# mic_sensor_arduino.net
KiCad netlist of a schematic drawn in EAGLE
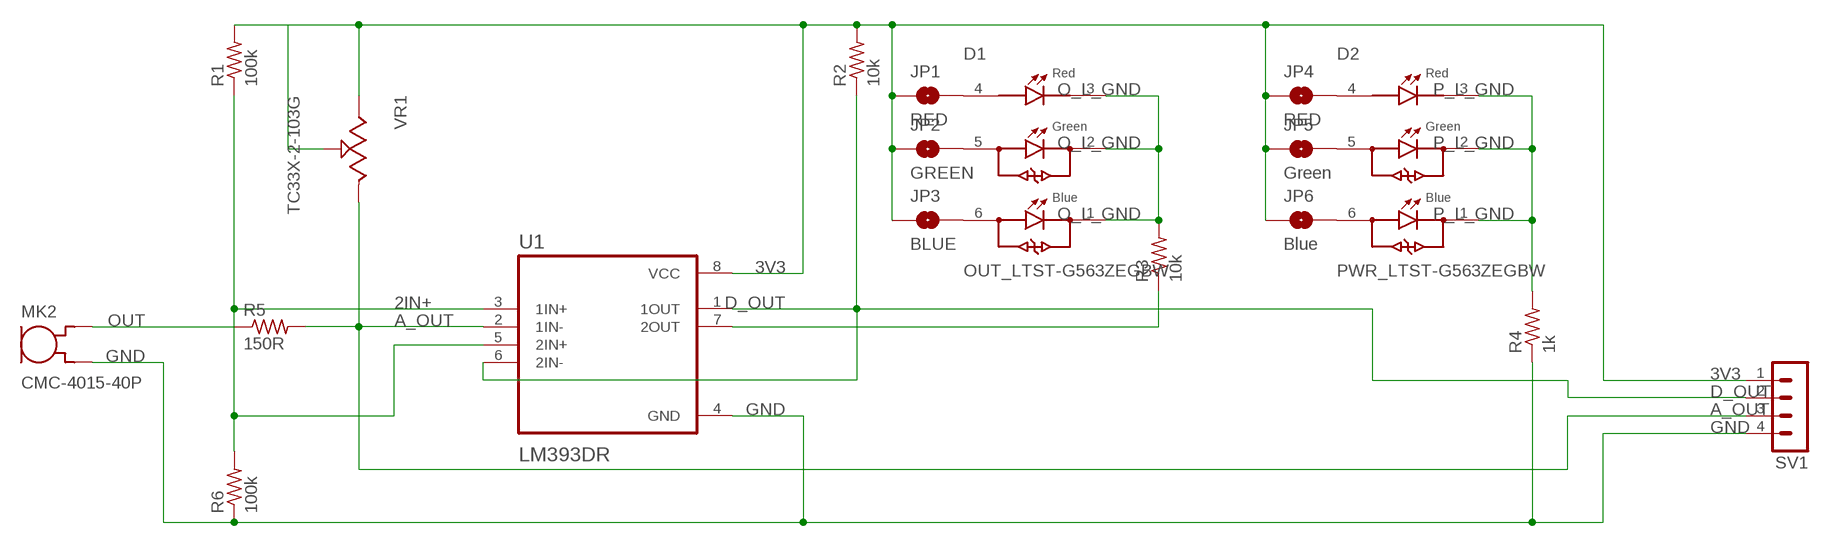
[diagram p0: schematic, sheet 1]

(export (version "E")
  (design (tool "Eeschema 10.0.6"))
  (components
    (comp (ref "D1")
      (value "OUT_LTST-G563ZEGBW")
      (footprint "eagle-import:LED_LTST-G563ZEGBW")
      (fields (field (name "MF") "Lite-On") (field (name "MP") "LTST-G563ZEGBW"))
      (libsource (lib "eagle-import") (part "LTST-G563ZEGBW"))
    )
    (comp (ref "D2")
      (value "PWR_LTST-G563ZEGBW")
      (footprint "eagle-import:LED_LTST-G563ZEGBW")
      (fields (field (name "MF") "Lite-On") (field (name "MP") "LTST-G563ZEGBW"))
      (libsource (lib "eagle-import") (part "LTST-G563ZEGBW"))
    )
    (comp (ref "JP1")
      (value "RED")
      (footprint "eagle-import:SMT-JUMPER_2_NO_SILK")
      (libsource (lib "eagle-import") (part "JUMPER-SMT_2_NO_SILK"))
    )
    (comp (ref "JP2")
      (value "GREEN")
      (footprint "eagle-import:SMT-JUMPER_2_NO_SILK")
      (libsource (lib "eagle-import") (part "JUMPER-SMT_2_NO_SILK"))
    )
    (comp (ref "JP3")
      (value "BLUE")
      (footprint "eagle-import:SMT-JUMPER_2_NO_SILK")
      (libsource (lib "eagle-import") (part "JUMPER-SMT_2_NO_SILK"))
    )
    (comp (ref "JP4")
      (value "RED")
      (footprint "eagle-import:SMT-JUMPER_2_NO_SILK")
      (libsource (lib "eagle-import") (part "JUMPER-SMT_2_NO_SILK"))
    )
    (comp (ref "JP5")
      (value "Green")
      (footprint "eagle-import:SMT-JUMPER_2_NO_SILK")
      (libsource (lib "eagle-import") (part "JUMPER-SMT_2_NO_SILK"))
    )
    (comp (ref "JP6")
      (value "Blue")
      (footprint "eagle-import:SMT-JUMPER_2_NO_SILK")
      (libsource (lib "eagle-import") (part "JUMPER-SMT_2_NO_SILK"))
    )
    (comp (ref "MK2")
      (value "CMC-4015-40P")
      (footprint "eagle-import:MIC_CMC-4015-40P")
      (fields (field (name "MF") "CUI Devices"))
      (libsource (lib "eagle-import") (part "CMC-4015-40P"))
    )
    (comp (ref "R1")
      (value "100k")
      (footprint "eagle-import:R0603")
      (libsource (lib "eagle-import") (part "R-US_R0603"))
    )
    (comp (ref "R2")
      (value "10k")
      (footprint "eagle-import:R0603")
      (libsource (lib "eagle-import") (part "R-US_R0603"))
    )
    (comp (ref "R3")
      (value "10k")
      (footprint "eagle-import:R0603")
      (libsource (lib "eagle-import") (part "R-US_R0603"))
    )
    (comp (ref "R4")
      (value "1k")
      (footprint "eagle-import:R0603")
      (libsource (lib "eagle-import") (part "R-US_R0603"))
    )
    (comp (ref "R5")
      (value "150R")
      (footprint "eagle-import:R0603")
      (libsource (lib "eagle-import") (part "R-US_R0603"))
    )
    (comp (ref "R6")
      (value "100k")
      (footprint "eagle-import:R0603")
      (libsource (lib "eagle-import") (part "R-US_R0603"))
    )
    (comp (ref "SV1")
      (value "MA04-1")
      (footprint "eagle-import:MA04-1")
      (libsource (lib "eagle-import") (part "MA04-1"))
    )
    (comp (ref "U1")
      (value "LM393DR")
      (footprint "eagle-import:SOIC127P599X175-8N")
      (fields (field (name "MF") "Texas Instruments"))
      (libsource (lib "eagle-import") (part "LM393DR"))
    )
    (comp (ref "VR1")
      (value "TC33X-2-103G")
      (footprint "eagle-import:TRIMMER_TC33X-2-103G")
      (fields (field (name "MF") "Bourns"))
      (libsource (lib "eagle-import") (part "TC33X-2-103G"))
    )
  )
  (nets
    (net (code "1") (name "/2IN+") (class "Default")
      (node (ref "R1") (pin "1") (pinfunction "1_1") (pintype "passive"))
      (node (ref "R6") (pin "2") (pinfunction "2_2") (pintype "passive"))
      (node (ref "U1") (pin "3") (pinfunction "1IN+_3") (pintype "input"))
      (node (ref "U1") (pin "5") (pinfunction "2IN+_5") (pintype "input"))
    )
    (net (code "2") (name "/3V3") (class "Default")
      (node (ref "JP1") (pin "1") (pinfunction "1_1") (pintype "passive"))
      (node (ref "JP2") (pin "1") (pinfunction "1_1") (pintype "passive"))
      (node (ref "JP3") (pin "1") (pinfunction "1_1") (pintype "passive"))
      (node (ref "JP4") (pin "1") (pinfunction "1_1") (pintype "passive"))
      (node (ref "JP5") (pin "1") (pinfunction "1_1") (pintype "passive"))
      (node (ref "JP6") (pin "1") (pinfunction "1_1") (pintype "passive"))
      (node (ref "R1") (pin "2") (pinfunction "2_2") (pintype "passive"))
      (node (ref "R2") (pin "2") (pinfunction "2_2") (pintype "passive"))
      (node (ref "SV1") (pin "1") (pinfunction "1_1") (pintype "passive"))
      (node (ref "U1") (pin "8") (pinfunction "VCC_8") (pintype "power_in"))
      (node (ref "VR1") (pin "1") (pinfunction "CCW_1") (pintype "passive"))
      (node (ref "VR1") (pin "2") (pinfunction "WIPER_2") (pintype "passive"))
    )
    (net (code "3") (name "/A_OUT") (class "Default")
      (node (ref "R5") (pin "2") (pinfunction "2_2") (pintype "passive"))
      (node (ref "SV1") (pin "3") (pinfunction "3_3") (pintype "passive"))
      (node (ref "U1") (pin "2") (pinfunction "1IN-_2") (pintype "input"))
      (node (ref "VR1") (pin "3") (pinfunction "CW_3") (pintype "passive"))
    )
    (net (code "4") (name "/D_OUT") (class "Default")
      (node (ref "R2") (pin "1") (pinfunction "1_1") (pintype "passive"))
      (node (ref "SV1") (pin "2") (pinfunction "2_2") (pintype "passive"))
      (node (ref "U1") (pin "1") (pinfunction "1OUT_1") (pintype "output"))
      (node (ref "U1") (pin "6") (pinfunction "2IN-_6") (pintype "input"))
    )
    (net (code "5") (name "/GND") (class "Default")
      (node (ref "MK2") (pin "M") (pinfunction "GND_M") (pintype "power_in"))
      (node (ref "R4") (pin "1") (pinfunction "1_1") (pintype "passive"))
      (node (ref "R6") (pin "1") (pinfunction "1_1") (pintype "passive"))
      (node (ref "SV1") (pin "4") (pinfunction "4_4") (pintype "passive"))
      (node (ref "U1") (pin "4") (pinfunction "GND_4") (pintype "power_in"))
    )
    (net (code "6") (name "/OUT") (class "Default")
      (node (ref "MK2") (pin "P") (pinfunction "OUT_P") (pintype "output"))
      (node (ref "R5") (pin "1") (pinfunction "1_1") (pintype "passive"))
    )
    (net (code "7") (name "/O_L_GND") (class "Default")
      (node (ref "D1") (pin "1") (pinfunction "1_1") (pintype "passive"))
      (node (ref "D1") (pin "2") (pinfunction "2_2") (pintype "passive"))
      (node (ref "D1") (pin "3") (pinfunction "3_3") (pintype "passive"))
      (node (ref "R3") (pin "2") (pinfunction "2_2") (pintype "passive"))
    )
    (net (code "8") (name "/P_L_GND") (class "Default")
      (node (ref "D2") (pin "1") (pinfunction "1_1") (pintype "passive"))
      (node (ref "D2") (pin "2") (pinfunction "2_2") (pintype "passive"))
      (node (ref "D2") (pin "3") (pinfunction "3_3") (pintype "passive"))
      (node (ref "R4") (pin "2") (pinfunction "2_2") (pintype "passive"))
    )
    (net (code "9") (name "Net-(D1-Pad4)") (class "Default")
      (node (ref "D1") (pin "4") (pinfunction "4_4") (pintype "passive"))
      (node (ref "JP1") (pin "2") (pinfunction "2_2") (pintype "passive"))
    )
    (net (code "10") (name "Net-(D1-Pad5)") (class "Default")
      (node (ref "D1") (pin "5") (pinfunction "5_5") (pintype "passive"))
      (node (ref "JP2") (pin "2") (pinfunction "2_2") (pintype "passive"))
    )
    (net (code "11") (name "Net-(D1-Pad6)") (class "Default")
      (node (ref "D1") (pin "6") (pinfunction "6_6") (pintype "passive"))
      (node (ref "JP3") (pin "2") (pinfunction "2_2") (pintype "passive"))
    )
    (net (code "12") (name "Net-(D2-Pad4)") (class "Default")
      (node (ref "D2") (pin "4") (pinfunction "4_4") (pintype "passive"))
      (node (ref "JP4") (pin "2") (pinfunction "2_2") (pintype "passive"))
    )
    (net (code "13") (name "Net-(D2-Pad5)") (class "Default")
      (node (ref "D2") (pin "5") (pinfunction "5_5") (pintype "passive"))
      (node (ref "JP5") (pin "2") (pinfunction "2_2") (pintype "passive"))
    )
    (net (code "14") (name "Net-(D2-Pad6)") (class "Default")
      (node (ref "D2") (pin "6") (pinfunction "6_6") (pintype "passive"))
      (node (ref "JP6") (pin "2") (pinfunction "2_2") (pintype "passive"))
    )
    (net (code "15") (name "Net-(U1-2OUT)") (class "Default")
      (node (ref "R3") (pin "1") (pinfunction "1_1") (pintype "passive"))
      (node (ref "U1") (pin "7") (pinfunction "2OUT_7") (pintype "output"))
    )
  )
)
